# ctrl_encoder.net
KiCad netlist of a schematic drawn in EAGLE
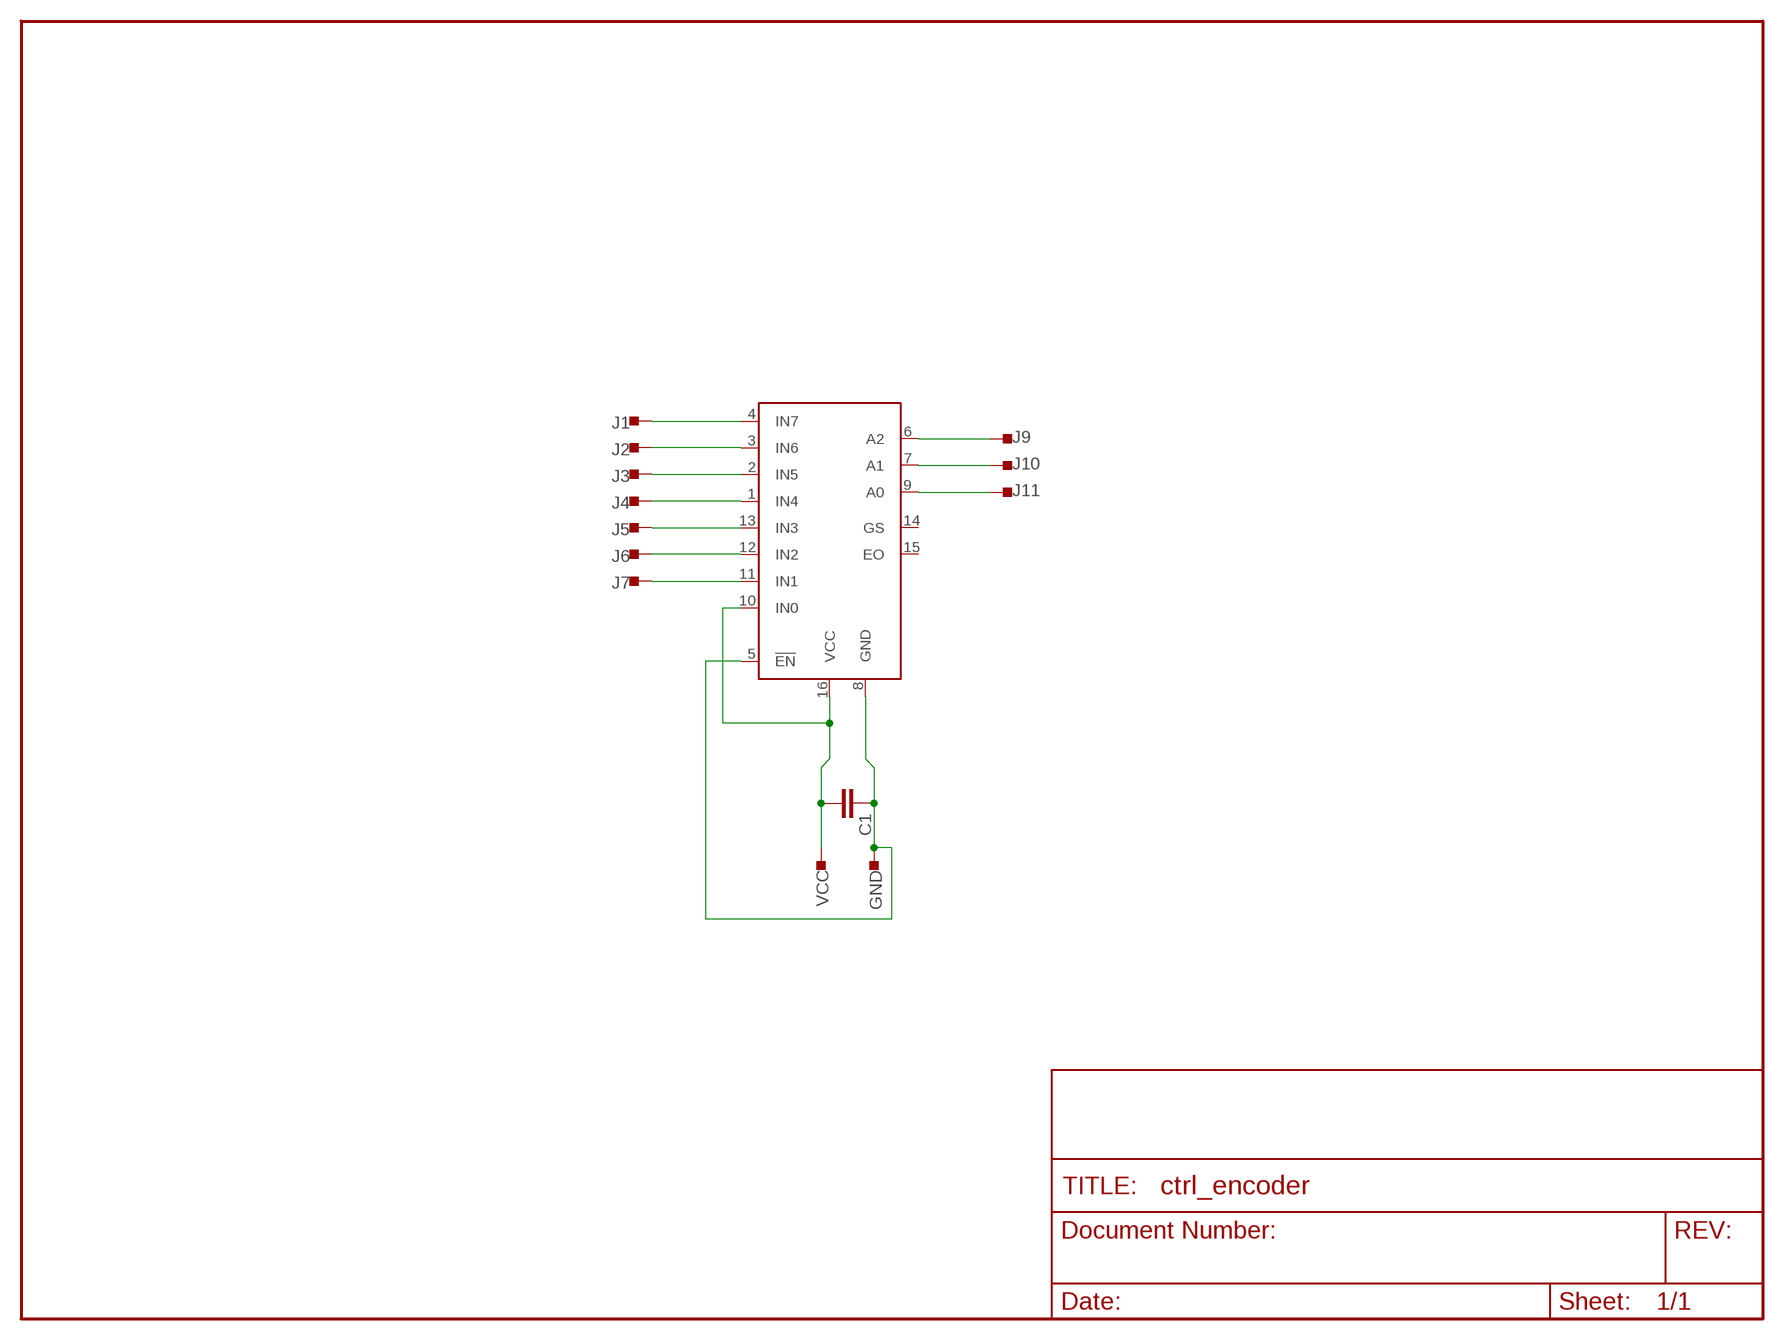
[diagram p0: schematic, sheet 1]

(export (version "E")
  (design (tool "Eeschema 10.0.6"))
  (components
    (comp (ref "C1") (value "C") (footprint "eagle-import:C0805") (libsource (lib "eagle-import") (part "C")))
    (comp (ref "GND")
      (value "PAD")
      (footprint "eagle-import:TEST_PAD")
      (libsource (lib "eagle-import") (part "PAD"))
    )
    (comp (ref "J1")
      (value "PAD")
      (footprint "eagle-import:TEST_PAD")
      (libsource (lib "eagle-import") (part "PAD"))
    )
    (comp (ref "J2")
      (value "PAD")
      (footprint "eagle-import:TEST_PAD")
      (libsource (lib "eagle-import") (part "PAD"))
    )
    (comp (ref "J3")
      (value "PAD")
      (footprint "eagle-import:TEST_PAD")
      (libsource (lib "eagle-import") (part "PAD"))
    )
    (comp (ref "J4")
      (value "PAD")
      (footprint "eagle-import:TEST_PAD")
      (libsource (lib "eagle-import") (part "PAD"))
    )
    (comp (ref "J5")
      (value "PAD")
      (footprint "eagle-import:TEST_PAD")
      (libsource (lib "eagle-import") (part "PAD"))
    )
    (comp (ref "J6")
      (value "PAD")
      (footprint "eagle-import:TEST_PAD")
      (libsource (lib "eagle-import") (part "PAD"))
    )
    (comp (ref "J7")
      (value "PAD")
      (footprint "eagle-import:TEST_PAD")
      (libsource (lib "eagle-import") (part "PAD"))
    )
    (comp (ref "J9")
      (value "PAD")
      (footprint "eagle-import:TEST_PAD")
      (libsource (lib "eagle-import") (part "PAD"))
    )
    (comp (ref "J10")
      (value "PAD")
      (footprint "eagle-import:TEST_PAD")
      (libsource (lib "eagle-import") (part "PAD"))
    )
    (comp (ref "J11")
      (value "PAD")
      (footprint "eagle-import:TEST_PAD")
      (libsource (lib "eagle-import") (part "PAD"))
    )
    (comp (ref "U$1")
      (value "SN74HC148DR")
      (footprint "eagle-import:SO16")
      (libsource (lib "eagle-import") (part "SN74HC148DR"))
    )
    (comp (ref "VCC")
      (value "PAD")
      (footprint "eagle-import:TEST_PAD")
      (libsource (lib "eagle-import") (part "PAD"))
    )
  )
  (nets
    (net (code "1") (name "Net-(GND-PAD)") (class "Default")
      (node (ref "C1") (pin "1") (pinfunction "1_1") (pintype "passive"))
      (node (ref "GND") (pin "P$1") (pinfunction "PAD_P$1") (pintype "passive"))
      (node (ref "U$1") (pin "5") (pinfunction "~{EN}_5") (pintype "bidirectional"))
      (node (ref "U$1") (pin "8") (pinfunction "GND_8") (pintype "power_in"))
    )
    (net (code "2") (name "Net-(J1-PAD)") (class "Default")
      (node (ref "J1") (pin "P$1") (pinfunction "PAD_P$1") (pintype "passive"))
      (node (ref "U$1") (pin "4") (pinfunction "IN7_4") (pintype "input"))
    )
    (net (code "3") (name "Net-(J2-PAD)") (class "Default")
      (node (ref "J2") (pin "P$1") (pinfunction "PAD_P$1") (pintype "passive"))
      (node (ref "U$1") (pin "3") (pinfunction "IN6_3") (pintype "input"))
    )
    (net (code "4") (name "Net-(J3-PAD)") (class "Default")
      (node (ref "J3") (pin "P$1") (pinfunction "PAD_P$1") (pintype "passive"))
      (node (ref "U$1") (pin "2") (pinfunction "IN5_2") (pintype "input"))
    )
    (net (code "5") (name "Net-(J4-PAD)") (class "Default")
      (node (ref "J4") (pin "P$1") (pinfunction "PAD_P$1") (pintype "passive"))
      (node (ref "U$1") (pin "1") (pinfunction "IN4_1") (pintype "input"))
    )
    (net (code "6") (name "Net-(J5-PAD)") (class "Default")
      (node (ref "J5") (pin "P$1") (pinfunction "PAD_P$1") (pintype "passive"))
      (node (ref "U$1") (pin "13") (pinfunction "IN3_13") (pintype "input"))
    )
    (net (code "7") (name "Net-(J6-PAD)") (class "Default")
      (node (ref "J6") (pin "P$1") (pinfunction "PAD_P$1") (pintype "passive"))
      (node (ref "U$1") (pin "12") (pinfunction "IN2_12") (pintype "input"))
    )
    (net (code "8") (name "Net-(J7-PAD)") (class "Default")
      (node (ref "J7") (pin "P$1") (pinfunction "PAD_P$1") (pintype "passive"))
      (node (ref "U$1") (pin "11") (pinfunction "IN1_11") (pintype "input"))
    )
    (net (code "9") (name "Net-(J9-PAD)") (class "Default")
      (node (ref "J9") (pin "P$1") (pinfunction "PAD_P$1") (pintype "passive"))
      (node (ref "U$1") (pin "6") (pinfunction "A2_6") (pintype "output"))
    )
    (net (code "10") (name "Net-(J10-PAD)") (class "Default")
      (node (ref "J10") (pin "P$1") (pinfunction "PAD_P$1") (pintype "passive"))
      (node (ref "U$1") (pin "7") (pinfunction "A1_7") (pintype "output"))
    )
    (net (code "11") (name "Net-(J11-PAD)") (class "Default")
      (node (ref "J11") (pin "P$1") (pinfunction "PAD_P$1") (pintype "passive"))
      (node (ref "U$1") (pin "9") (pinfunction "A0_9") (pintype "output"))
    )
    (net (code "12") (name "Net-(U$1-IN0)") (class "Default")
      (node (ref "C1") (pin "2") (pinfunction "2_2") (pintype "passive"))
      (node (ref "U$1") (pin "10") (pinfunction "IN0_10") (pintype "input"))
      (node (ref "U$1") (pin "16") (pinfunction "VCC_16") (pintype "power_in"))
      (node (ref "VCC") (pin "P$1") (pinfunction "PAD_P$1") (pintype "passive"))
    )
    (net (code "13") (name "unconnected-(U$1-EO-Pad15)") (class "Default")
      (node (ref "U$1") (pin "15") (pinfunction "EO_15") (pintype "output"))
    )
    (net (code "14") (name "unconnected-(U$1-GS-Pad14)") (class "Default")
      (node (ref "U$1") (pin "14") (pinfunction "GS_14") (pintype "output"))
    )
  )
)
